# WIFI_and_BLE.net
KiCad netlist of a schematic drawn in Altium Designer
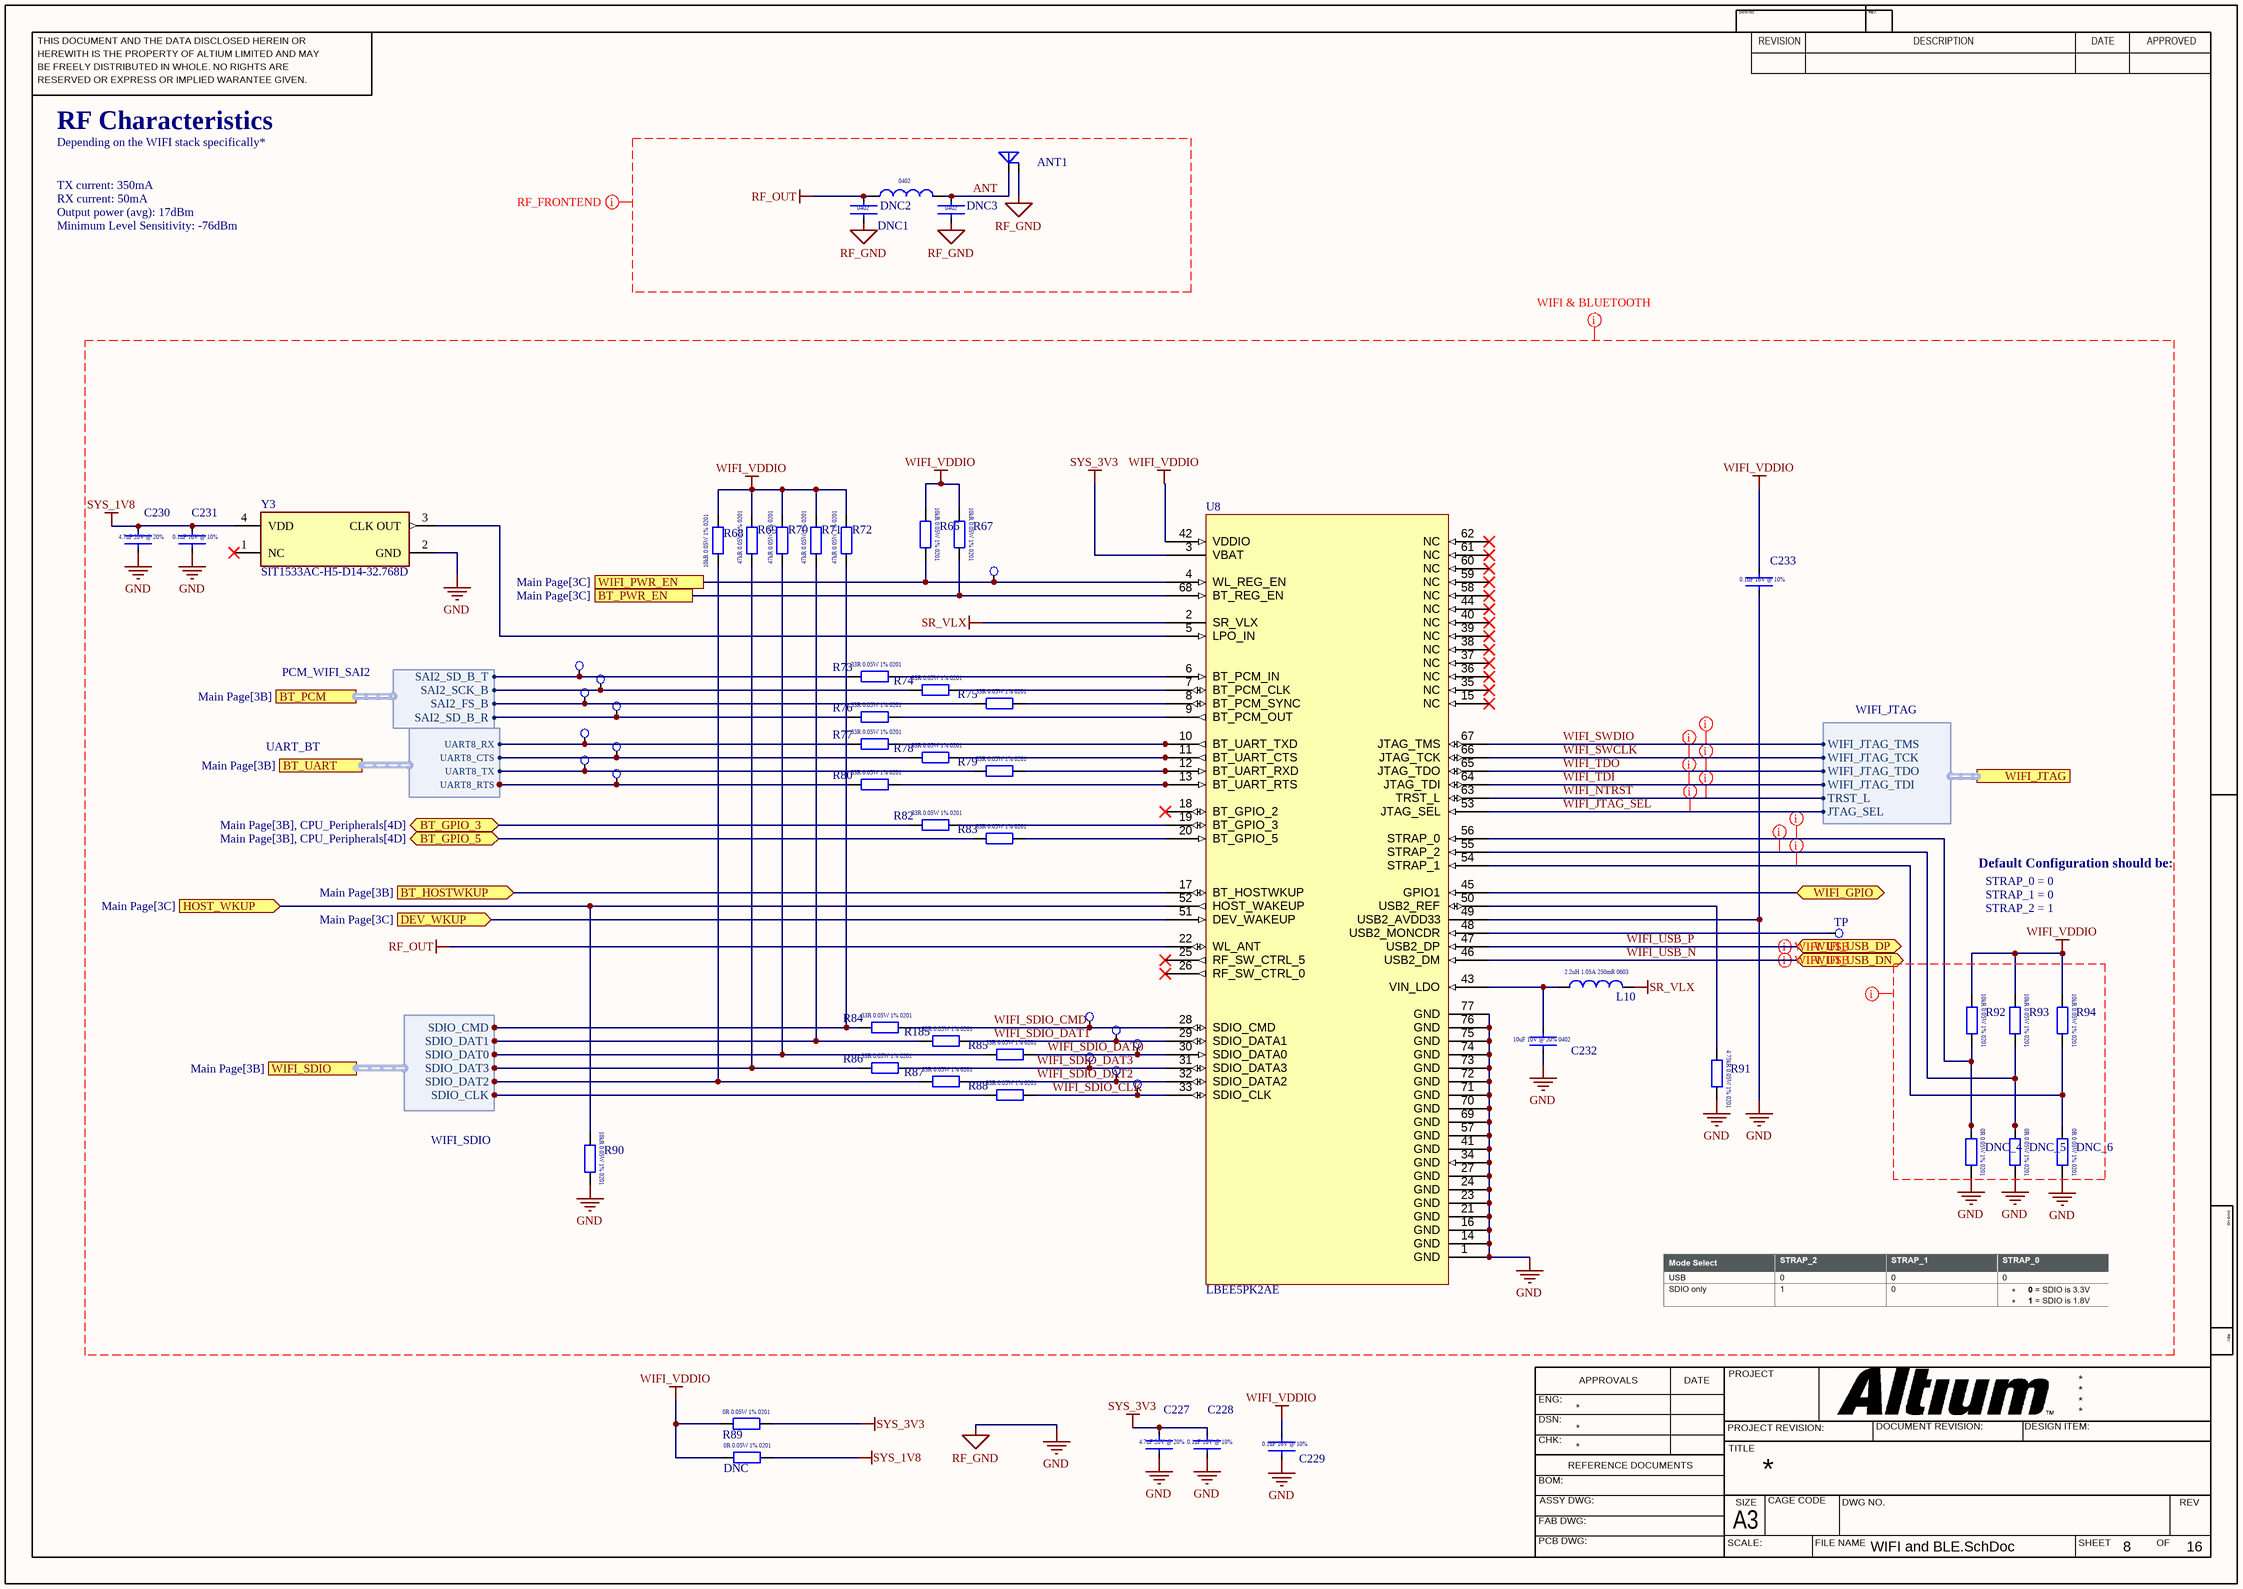
[diagram p0: WIFI and BLE.SchDoc]

(export (version "E")
  (design (tool "Eeschema 10.0.6"))
  (components
    (comp (ref "ANT1")
      (value "ANT5320LL24R2455A")
      (footprint "ANT5320LL24R2455A")
      (description "RF ANTENNA WLAN Chip Solder Surface Mount")
      (libsource (lib "Gesturelink Schematic Library") (part "ANT5320LL24R2455A"))
    )
    (comp (ref "C227")
      (value "4.7uF")
      (footprint "CAPC1005X06L")
      (description "4.7 µF ±20% 16V Ceramic Capacitor X5R 0402 (1005 Metric)")
      (libsource (lib "Gesturelink Schematic Library") (part "CL05A475MO5NUNC"))
    )
    (comp (ref "C228")
      (value "0.1uF")
      (footprint "CAPC0603X03L")
      (libsource (lib "Gesturelink Schematic Library") (part "GRM033R61E104KE14J"))
    )
    (comp (ref "C229")
      (value "0.1uF")
      (footprint "CAPC0603X03L")
      (libsource (lib "Gesturelink Schematic Library") (part "GRM033R61E104KE14J"))
    )
    (comp (ref "C230")
      (value "4.7uF")
      (footprint "CAPC1005X06L")
      (description "4.7 µF ±20% 16V Ceramic Capacitor X5R 0402 (1005 Metric)")
      (libsource (lib "Gesturelink Schematic Library") (part "CL05A475MO5NUNC"))
    )
    (comp (ref "C231")
      (value "0.1uF")
      (footprint "CAPC0603X03L")
      (libsource (lib "Gesturelink Schematic Library") (part "GRM033R61E104KE14J"))
    )
    (comp (ref "C232")
      (value "GRT155R61A106ME13J")
      (footprint "CAPC1005X06L")
      (description "10 µF ±20% 10V Ceramic Capacitor X5R 0402 (1005 Metric)")
      (libsource (lib "Capacitors") (part "GRT155R61A106ME13J"))
    )
    (comp (ref "C233")
      (value "0.1uF")
      (footprint "CAPC0603X03L")
      (libsource (lib "Gesturelink Schematic Library") (part "GRM033R61E104KE14J"))
    )
    (comp (ref "DNC")
      (value "ERJ-1GN0R00C")
      (footprint "RESC0603X03L")
      (description "0 Ohms Jumper Chip Resistor 0201 (0603 Metric) Thick Film")
      (libsource (lib "") (part "ERJ-1GN0R00C_1"))
    )
    (comp (ref "DNC1")
      (value "RF_GND_PI")
      (footprint "CAPC1005X06L")
      (description "Pi filter chip antenna, Do not connect!")
      (libsource (lib "Gesturelink Schematic Library") (part "RF_GND_PI"))
    )
    (comp (ref "DNC2")
      (value "DNC RF Inductor")
      (footprint "RESC1005X04L")
      (description "Inductor for PI filter, DNC")
      (libsource (lib "Inductors") (part "DNC RF Inductor"))
    )
    (comp (ref "DNC3")
      (value "RF_GND_PI")
      (footprint "CAPC1005X06L")
      (description "Pi filter chip antenna, Do not connect!")
      (libsource (lib "Gesturelink Schematic Library") (part "RF_GND_PI"))
    )
    (comp (ref "DNC_4")
      (value "ERJ-1GN0R00C")
      (footprint "RESC0603X03L")
      (description "0 Ohms Jumper Chip Resistor 0201 (0603 Metric) Thick Film")
      (libsource (lib "Resistors") (part "ERJ-1GN0R00C"))
    )
    (comp (ref "DNC_5")
      (value "ERJ-1GN0R00C")
      (footprint "RESC0603X03L")
      (description "0 Ohms Jumper Chip Resistor 0201 (0603 Metric) Thick Film")
      (libsource (lib "Resistors") (part "ERJ-1GN0R00C"))
    )
    (comp (ref "DNC_6")
      (value "ERJ-1GN0R00C")
      (footprint "RESC0603X03L")
      (description "0 Ohms Jumper Chip Resistor 0201 (0603 Metric) Thick Film")
      (libsource (lib "Resistors") (part "ERJ-1GN0R00C"))
    )
    (comp (ref "L10")
      (value "LQM18PN2R2MGHD")
      (footprint "INDC1608LPX08L")
      (description "2.2 µH Shielded Multilayer Inductor 1.05 A 250mOhm Max 0603 (1608 Metric)")
      (libsource (lib "Inductors") (part "LQM18PN2R2MGHD"))
    )
    (comp (ref "R66")
      (value "ERJ-1GNF1002C")
      (footprint "RESC0603X03L")
      (description "10 kOhms ±1% 0.05W, 1/20W Chip Resistor 0201 (0603 Metric) Thick Film")
      (libsource (lib "Resistors") (part "ERJ-1GNF1002C"))
    )
    (comp (ref "R67")
      (value "ERJ-1GNF1002C")
      (footprint "RESC0603X03L")
      (description "10 kOhms ±1% 0.05W, 1/20W Chip Resistor 0201 (0603 Metric) Thick Film")
      (libsource (lib "Resistors") (part "ERJ-1GNF1002C"))
    )
    (comp (ref "R68")
      (value "ERJ-1GNF1002C")
      (footprint "RESC0603X03L")
      (description "10 kOhms ±1% 0.05W, 1/20W Chip Resistor 0201 (0603 Metric) Thick Film")
      (libsource (lib "") (part "ERJ-1GNF1002C_1"))
    )
    (comp (ref "R69")
      (value "AC0201FR-0747KL")
      (footprint "RESC0603X03L")
      (libsource (lib "Resistors") (part "AC0201FR-0747KL"))
    )
    (comp (ref "R70")
      (value "AC0201FR-0747KL")
      (footprint "RESC0603X03L")
      (libsource (lib "Resistors") (part "AC0201FR-0747KL"))
    )
    (comp (ref "R71")
      (value "AC0201FR-0747KL")
      (footprint "RESC0603X03L")
      (libsource (lib "Resistors") (part "AC0201FR-0747KL"))
    )
    (comp (ref "R72")
      (value "AC0201FR-0747KL")
      (footprint "RESC0603X03L")
      (libsource (lib "Resistors") (part "AC0201FR-0747KL"))
    )
    (comp (ref "R73")
      (value "ERJ-1GNF33R0C")
      (footprint "RESC0603X03L")
      (description "33 Ohms ±1% 0.05W, 1/20W Chip Resistor 0201 (0603 Metric) Thick Film")
      (libsource (lib "Resistors") (part "ERJ-1GNF33R0C"))
    )
    (comp (ref "R74")
      (value "ERJ-1GNF33R0C")
      (footprint "RESC0603X03L")
      (description "33 Ohms ±1% 0.05W, 1/20W Chip Resistor 0201 (0603 Metric) Thick Film")
      (libsource (lib "Resistors") (part "ERJ-1GNF33R0C"))
    )
    (comp (ref "R75")
      (value "ERJ-1GNF33R0C")
      (footprint "RESC0603X03L")
      (description "33 Ohms ±1% 0.05W, 1/20W Chip Resistor 0201 (0603 Metric) Thick Film")
      (libsource (lib "Resistors") (part "ERJ-1GNF33R0C"))
    )
    (comp (ref "R76")
      (value "ERJ-1GNF33R0C")
      (footprint "RESC0603X03L")
      (description "33 Ohms ±1% 0.05W, 1/20W Chip Resistor 0201 (0603 Metric) Thick Film")
      (libsource (lib "Resistors") (part "ERJ-1GNF33R0C"))
    )
    (comp (ref "R77")
      (value "ERJ-1GNF33R0C")
      (footprint "RESC0603X03L")
      (description "33 Ohms ±1% 0.05W, 1/20W Chip Resistor 0201 (0603 Metric) Thick Film")
      (libsource (lib "Resistors") (part "ERJ-1GNF33R0C"))
    )
    (comp (ref "R78")
      (value "ERJ-1GNF33R0C")
      (footprint "RESC0603X03L")
      (description "33 Ohms ±1% 0.05W, 1/20W Chip Resistor 0201 (0603 Metric) Thick Film")
      (libsource (lib "Resistors") (part "ERJ-1GNF33R0C"))
    )
    (comp (ref "R79")
      (value "ERJ-1GNF33R0C")
      (footprint "RESC0603X03L")
      (description "33 Ohms ±1% 0.05W, 1/20W Chip Resistor 0201 (0603 Metric) Thick Film")
      (libsource (lib "Resistors") (part "ERJ-1GNF33R0C"))
    )
    (comp (ref "R80")
      (value "ERJ-1GNF33R0C")
      (footprint "RESC0603X03L")
      (description "33 Ohms ±1% 0.05W, 1/20W Chip Resistor 0201 (0603 Metric) Thick Film")
      (libsource (lib "Resistors") (part "ERJ-1GNF33R0C"))
    )
    (comp (ref "R82")
      (value "ERJ-1GNF33R0C")
      (footprint "RESC0603X03L")
      (description "33 Ohms ±1% 0.05W, 1/20W Chip Resistor 0201 (0603 Metric) Thick Film")
      (libsource (lib "Resistors") (part "ERJ-1GNF33R0C"))
    )
    (comp (ref "R83")
      (value "ERJ-1GNF33R0C")
      (footprint "RESC0603X03L")
      (description "33 Ohms ±1% 0.05W, 1/20W Chip Resistor 0201 (0603 Metric) Thick Film")
      (libsource (lib "Resistors") (part "ERJ-1GNF33R0C"))
    )
    (comp (ref "R84")
      (value "ERJ-1GNF33R0C")
      (footprint "RESC0603X03L")
      (description "33 Ohms ±1% 0.05W, 1/20W Chip Resistor 0201 (0603 Metric) Thick Film")
      (libsource (lib "Resistors") (part "ERJ-1GNF33R0C"))
    )
    (comp (ref "R85")
      (value "ERJ-1GNF33R0C")
      (footprint "RESC0603X03L")
      (description "33 Ohms ±1% 0.05W, 1/20W Chip Resistor 0201 (0603 Metric) Thick Film")
      (libsource (lib "Resistors") (part "ERJ-1GNF33R0C"))
    )
    (comp (ref "R86")
      (value "ERJ-1GNF33R0C")
      (footprint "RESC0603X03L")
      (description "33 Ohms ±1% 0.05W, 1/20W Chip Resistor 0201 (0603 Metric) Thick Film")
      (libsource (lib "Resistors") (part "ERJ-1GNF33R0C"))
    )
    (comp (ref "R87")
      (value "ERJ-1GNF33R0C")
      (footprint "RESC0603X03L")
      (description "33 Ohms ±1% 0.05W, 1/20W Chip Resistor 0201 (0603 Metric) Thick Film")
      (libsource (lib "Resistors") (part "ERJ-1GNF33R0C"))
    )
    (comp (ref "R88")
      (value "ERJ-1GNF33R0C")
      (footprint "RESC0603X03L")
      (description "33 Ohms ±1% 0.05W, 1/20W Chip Resistor 0201 (0603 Metric) Thick Film")
      (libsource (lib "Resistors") (part "ERJ-1GNF33R0C"))
    )
    (comp (ref "R89")
      (value "ERJ-1GN0R00C")
      (footprint "RESC0603X03L")
      (description "0 Ohms Jumper Chip Resistor 0201 (0603 Metric) Thick Film")
      (libsource (lib "") (part "ERJ-1GN0R00C_1"))
    )
    (comp (ref "R90")
      (value "ERJ-1GNF1002C")
      (footprint "RESC0603X03L")
      (description "10 kOhms ±1% 0.05W, 1/20W Chip Resistor 0201 (0603 Metric) Thick Film")
      (libsource (lib "Resistors") (part "ERJ-1GNF1002C"))
    )
    (comp (ref "R91")
      (value "AC0201FR-074K75L")
      (footprint "RESC0603X03L")
      (libsource (lib "Resistors") (part "AC0201FR-074K75L"))
    )
    (comp (ref "R92")
      (value "ERJ-1GNF1002C")
      (footprint "RESC0603X03L")
      (description "10 kOhms ±1% 0.05W, 1/20W Chip Resistor 0201 (0603 Metric) Thick Film")
      (libsource (lib "Resistors") (part "ERJ-1GNF1002C"))
    )
    (comp (ref "R93")
      (value "ERJ-1GNF1002C")
      (footprint "RESC0603X03L")
      (description "10 kOhms ±1% 0.05W, 1/20W Chip Resistor 0201 (0603 Metric) Thick Film")
      (libsource (lib "Resistors") (part "ERJ-1GNF1002C"))
    )
    (comp (ref "R94")
      (value "ERJ-1GNF1002C")
      (footprint "RESC0603X03L")
      (description "10 kOhms ±1% 0.05W, 1/20W Chip Resistor 0201 (0603 Metric) Thick Film")
      (libsource (lib "Resistors") (part "ERJ-1GNF1002C"))
    )
    (comp (ref "R185")
      (value "ERJ-1GNF33R0C")
      (footprint "RESC0603X03L")
      (description "33 Ohms ±1% 0.05W, 1/20W Chip Resistor 0201 (0603 Metric) Thick Film")
      (libsource (lib "Resistors") (part "ERJ-1GNF33R0C"))
    )
    (comp (ref "TP")
      (value "Test Point")
      (footprint "Test Point")
      (libsource (lib "Gesturelink Schematic Library") (part "Test Point"))
    )
    (comp (ref "TP1")
      (value "Test Point")
      (footprint "Test Point")
      (libsource (lib "Gesturelink Schematic Library") (part "Test Point"))
    )
    (comp (ref "TP2")
      (value "Test Point")
      (footprint "Test Point")
      (libsource (lib "Gesturelink Schematic Library") (part "Test Point"))
    )
    (comp (ref "TP3")
      (value "Test Point")
      (footprint "Test Point")
      (libsource (lib "Gesturelink Schematic Library") (part "Test Point"))
    )
    (comp (ref "TP4")
      (value "Test Point")
      (footprint "Test Point")
      (libsource (lib "Gesturelink Schematic Library") (part "Test Point"))
    )
    (comp (ref "TP5")
      (value "Test Point")
      (footprint "Test Point")
      (libsource (lib "Gesturelink Schematic Library") (part "Test Point"))
    )
    (comp (ref "TP6")
      (value "Test Point")
      (footprint "Test Point")
      (libsource (lib "Gesturelink Schematic Library") (part "Test Point"))
    )
    (comp (ref "TP21")
      (value "Test Point")
      (footprint "Test Point")
      (libsource (lib "Gesturelink Schematic Library") (part "Test Point"))
    )
    (comp (ref "TP22")
      (value "Test Point")
      (footprint "Test Point")
      (libsource (lib "Gesturelink Schematic Library") (part "Test Point"))
    )
    (comp (ref "TP23")
      (value "Test Point")
      (footprint "Test Point")
      (libsource (lib "Gesturelink Schematic Library") (part "Test Point"))
    )
    (comp (ref "TP24")
      (value "Test Point")
      (footprint "Test Point")
      (libsource (lib "Gesturelink Schematic Library") (part "Test Point"))
    )
    (comp (ref "TP25")
      (value "Test Point")
      (footprint "Test Point")
      (libsource (lib "Gesturelink Schematic Library") (part "Test Point"))
    )
    (comp (ref "TP26")
      (value "Test Point")
      (footprint "Test Point")
      (libsource (lib "Gesturelink Schematic Library") (part "Test Point"))
    )
    (comp (ref "TP27")
      (value "Test Point")
      (footprint "Test Point")
      (libsource (lib "Gesturelink Schematic Library") (part "Test Point"))
    )
    (comp (ref "TP28")
      (value "Test Point")
      (footprint "Test Point")
      (libsource (lib "Gesturelink Schematic Library") (part "Test Point"))
    )
    (comp (ref "TP40")
      (value "Test Point")
      (footprint "Test Point")
      (libsource (lib "Gesturelink Schematic Library") (part "Test Point"))
    )
    (comp (ref "U8")
      (value "LBEE5PK2AE")
      (footprint "LBEE5PK2AE")
      (libsource (lib "Gesturelink Schematic Library") (part "LBEE5PK2AE"))
    )
    (comp (ref "Y3")
      (value "SIT1533AC-H5-D14-32.768D")
      (footprint "FP-SiT1533-H-MFG")
      (description "MEMS OSC XO 32.7680KHZ LVCMOS")
      (libsource (lib "Altium Content Vault") (part "00febb3c8fa577a4e66d9d2e3688c3c"))
    )
  )
  (nets
    (net (code "5") (name "/ANT") (class "Default")
      (node (ref "ANT1") (pin "1") (pinfunction "FEED_1") (pintype "passive"))
      (node (ref "DNC2") (pin "2") (pinfunction "2_2") (pintype "passive"))
      (node (ref "DNC3") (pin "2") (pinfunction "2_2") (pintype "passive"))
    )
    (net (code "6") (name "/BT_GPIO_3") (class "Default")
      (node (ref "R82") (pin "1") (pinfunction "1_1") (pintype "passive"))
    )
    (net (code "7") (name "/BT_GPIO_5") (class "Default")
      (node (ref "R83") (pin "1") (pinfunction "1_1") (pintype "passive"))
    )
    (net (code "8") (name "/BT_HOSTWKUP") (class "Default")
      (node (ref "U8") (pin "17") (pinfunction "BT_HOSTWKUP_17") (pintype "bidirectional"))
    )
    (net (code "9") (name "/BT_PWR_EN") (class "Default")
      (node (ref "R67") (pin "2") (pinfunction "2_2") (pintype "passive"))
      (node (ref "U8") (pin "68") (pinfunction "BT_REG_EN_68") (pintype "input"))
    )
    (net (code "10") (name "/DEV_WKUP") (class "Default")
      (node (ref "U8") (pin "51") (pinfunction "DEV_WAKEUP_51") (pintype "input"))
    )
    (net (code "11") (name "/HOST_WKUP") (class "Default")
      (node (ref "R90") (pin "1") (pinfunction "1_1") (pintype "passive"))
      (node (ref "U8") (pin "52") (pinfunction "HOST_WAKEUP_52") (pintype "output"))
    )
    (net (code "12") (name "/SAI2_FS_B") (class "Default")
      (node (ref "R75") (pin "1") (pinfunction "1_1") (pintype "passive"))
      (node (ref "TP23") (pin "12") (pinfunction "12_12") (pintype "passive"))
    )
    (net (code "13") (name "/SAI2_SCK_B") (class "Default")
      (node (ref "R74") (pin "1") (pinfunction "1_1") (pintype "passive"))
      (node (ref "TP22") (pin "12") (pinfunction "12_12") (pintype "passive"))
    )
    (net (code "14") (name "/SAI2_SD_B_R") (class "Default")
      (node (ref "R76") (pin "1") (pinfunction "1_1") (pintype "passive"))
      (node (ref "TP24") (pin "12") (pinfunction "12_12") (pintype "passive"))
    )
    (net (code "15") (name "/SAI2_SD_B_T") (class "Default")
      (node (ref "R73") (pin "1") (pinfunction "1_1") (pintype "passive"))
      (node (ref "TP21") (pin "12") (pinfunction "12_12") (pintype "passive"))
    )
    (net (code "16") (name "/SDIO_CLK") (class "Default")
      (node (ref "R88") (pin "1") (pinfunction "1_1") (pintype "passive"))
    )
    (net (code "17") (name "/SDIO_CMD") (class "Default")
      (node (ref "R72") (pin "1") (pinfunction "1_1") (pintype "passive"))
      (node (ref "R84") (pin "1") (pinfunction "1_1") (pintype "passive"))
    )
    (net (code "18") (name "/SDIO_DAT0") (class "Default")
      (node (ref "R70") (pin "1") (pinfunction "1_1") (pintype "passive"))
      (node (ref "R85") (pin "1") (pinfunction "1_1") (pintype "passive"))
    )
    (net (code "19") (name "/SDIO_DAT1") (class "Default")
      (node (ref "R185") (pin "1") (pinfunction "1_1") (pintype "passive"))
      (node (ref "R71") (pin "1") (pinfunction "1_1") (pintype "passive"))
    )
    (net (code "20") (name "/SDIO_DAT2") (class "Default")
      (node (ref "R68") (pin "1") (pinfunction "1_1") (pintype "passive"))
      (node (ref "R87") (pin "1") (pinfunction "1_1") (pintype "passive"))
    )
    (net (code "21") (name "/SDIO_DAT3") (class "Default")
      (node (ref "R69") (pin "1") (pinfunction "1_1") (pintype "passive"))
      (node (ref "R86") (pin "1") (pinfunction "1_1") (pintype "passive"))
    )
    (net (code "22") (name "/UART8_CTS") (class "Default")
      (node (ref "R78") (pin "1") (pinfunction "1_1") (pintype "passive"))
      (node (ref "TP26") (pin "12") (pinfunction "12_12") (pintype "passive"))
    )
    (net (code "23") (name "/UART8_RTS") (class "Default")
      (node (ref "R80") (pin "1") (pinfunction "1_1") (pintype "passive"))
      (node (ref "TP28") (pin "12") (pinfunction "12_12") (pintype "passive"))
    )
    (net (code "24") (name "/UART8_RX") (class "Default")
      (node (ref "R77") (pin "1") (pinfunction "1_1") (pintype "passive"))
      (node (ref "TP25") (pin "12") (pinfunction "12_12") (pintype "passive"))
    )
    (net (code "25") (name "/UART8_TX") (class "Default")
      (node (ref "R79") (pin "1") (pinfunction "1_1") (pintype "passive"))
      (node (ref "TP27") (pin "12") (pinfunction "12_12") (pintype "passive"))
    )
    (net (code "26") (name "/WIFI_GPIO") (class "Default")
      (node (ref "U8") (pin "45") (pinfunction "GPIO1_45") (pintype "input"))
    )
    (net (code "27") (name "/WIFI_JTAG_SEL") (class "Default")
      (node (ref "U8") (pin "53") (pinfunction "JTAG_SEL_53") (pintype "input"))
    )
    (net (code "28") (name "/WIFI_NTRST") (class "Default")
      (node (ref "U8") (pin "63") (pinfunction "TRST_L_63") (pintype "bidirectional"))
    )
    (net (code "29") (name "/WIFI_PWR_EN") (class "Default")
      (node (ref "R66") (pin "2") (pinfunction "2_2") (pintype "passive"))
      (node (ref "TP40") (pin "12") (pinfunction "12_12") (pintype "passive"))
      (node (ref "U8") (pin "4") (pinfunction "WL_REG_EN_4") (pintype "input"))
    )
    (net (code "30") (name "/WIFI_SDIO_CLK") (class "Default")
      (node (ref "R88") (pin "2") (pinfunction "2_2") (pintype "passive"))
      (node (ref "TP6") (pin "12") (pinfunction "12_12") (pintype "passive"))
      (node (ref "U8") (pin "33") (pinfunction "SDIO_CLK_33") (pintype "bidirectional"))
    )
    (net (code "31") (name "/WIFI_SDIO_CMD") (class "Default")
      (node (ref "R84") (pin "2") (pinfunction "2_2") (pintype "passive"))
      (node (ref "TP1") (pin "12") (pinfunction "12_12") (pintype "passive"))
      (node (ref "U8") (pin "28") (pinfunction "SDIO_CMD_28") (pintype "bidirectional"))
    )
    (net (code "32") (name "/WIFI_SDIO_DAT0") (class "Default")
      (node (ref "R85") (pin "2") (pinfunction "2_2") (pintype "passive"))
      (node (ref "TP3") (pin "12") (pinfunction "12_12") (pintype "passive"))
      (node (ref "U8") (pin "30") (pinfunction "SDIO_DATA0_30") (pintype "input"))
    )
    (net (code "33") (name "/WIFI_SDIO_DAT1") (class "Default")
      (node (ref "R185") (pin "2") (pinfunction "2_2") (pintype "passive"))
      (node (ref "TP2") (pin "12") (pinfunction "12_12") (pintype "passive"))
      (node (ref "U8") (pin "29") (pinfunction "SDIO_DATA1_29") (pintype "bidirectional"))
    )
    (net (code "34") (name "/WIFI_SDIO_DAT2") (class "Default")
      (node (ref "R87") (pin "2") (pinfunction "2_2") (pintype "passive"))
      (node (ref "TP5") (pin "12") (pinfunction "12_12") (pintype "passive"))
      (node (ref "U8") (pin "32") (pinfunction "SDIO_DATA2_32") (pintype "bidirectional"))
    )
    (net (code "36") (name "/WIFI_SDIO_DAT3") (class "Default")
      (node (ref "R86") (pin "2") (pinfunction "2_2") (pintype "passive"))
      (node (ref "TP4") (pin "12") (pinfunction "12_12") (pintype "passive"))
      (node (ref "U8") (pin "31") (pinfunction "SDIO_DATA3_31") (pintype "bidirectional"))
    )
    (net (code "37") (name "/WIFI_SWCLK") (class "Default")
      (node (ref "U8") (pin "66") (pinfunction "JTAG_TCK_66") (pintype "bidirectional"))
    )
    (net (code "38") (name "/WIFI_SWDIO") (class "Default")
      (node (ref "U8") (pin "67") (pinfunction "JTAG_TMS_67") (pintype "bidirectional"))
    )
    (net (code "39") (name "/WIFI_TDI") (class "Default")
      (node (ref "U8") (pin "64") (pinfunction "JTAG_TDI_64") (pintype "bidirectional"))
    )
    (net (code "40") (name "/WIFI_TDO") (class "Default")
      (node (ref "U8") (pin "65") (pinfunction "JTAG_TDO_65") (pintype "bidirectional"))
    )
    (net (code "41") (name "/WIFI_USB_N") (class "Default")
      (node (ref "U8") (pin "46") (pinfunction "USB2_DM_46") (pintype "input"))
    )
    (net (code "46") (name "/WIFI_USB_P") (class "Default")
      (node (ref "U8") (pin "47") (pinfunction "USB2_DP_47") (pintype "input"))
    )
    (net (code "47") (name "GND") (class "Default")
      (node (ref "ANT1") (pin "3") (pinfunction "GND_3") (pintype "passive"))
      (node (ref "C227") (pin "1") (pinfunction "1_1") (pintype "passive"))
      (node (ref "C228") (pin "1") (pinfunction "1_1") (pintype "passive"))
      (node (ref "C229") (pin "1") (pinfunction "1_1") (pintype "passive"))
      (node (ref "C230") (pin "1") (pinfunction "1_1") (pintype "passive"))
      (node (ref "C231") (pin "1") (pinfunction "1_1") (pintype "passive"))
      (node (ref "C232") (pin "1") (pinfunction "1_1") (pintype "passive"))
      (node (ref "C233") (pin "1") (pinfunction "1_1") (pintype "passive"))
      (node (ref "DNC1") (pin "1") (pinfunction "1_1") (pintype "passive"))
      (node (ref "DNC3") (pin "1") (pinfunction "1_1") (pintype "passive"))
      (node (ref "DNC_4") (pin "2") (pinfunction "2_2") (pintype "passive"))
      (node (ref "DNC_5") (pin "2") (pinfunction "2_2") (pintype "passive"))
      (node (ref "DNC_6") (pin "2") (pinfunction "2_2") (pintype "passive"))
      (node (ref "R90") (pin "2") (pinfunction "2_2") (pintype "passive"))
      (node (ref "R91") (pin "2") (pinfunction "2_2") (pintype "passive"))
      (node (ref "U8") (pin "1") (pinfunction "GND_1") (pintype "power_in"))
      (node (ref "U8") (pin "14") (pinfunction "GND_14") (pintype "power_in"))
      (node (ref "U8") (pin "16") (pinfunction "GND_16") (pintype "power_in"))
      (node (ref "U8") (pin "21") (pinfunction "GND_21") (pintype "power_in"))
      (node (ref "U8") (pin "23") (pinfunction "GND_23") (pintype "power_in"))
      (node (ref "U8") (pin "24") (pinfunction "GND_24") (pintype "power_in"))
      (node (ref "U8") (pin "27") (pinfunction "GND_27") (pintype "power_in"))
      (node (ref "U8") (pin "34") (pinfunction "GND_34") (pintype "input"))
      (node (ref "U8") (pin "41") (pinfunction "GND_41") (pintype "power_in"))
      (node (ref "U8") (pin "49") (pinfunction "USB2_AVDD33_49") (pintype "power_in"))
      (node (ref "U8") (pin "57") (pinfunction "GND_57") (pintype "power_in"))
      (node (ref "U8") (pin "69") (pinfunction "GND_69") (pintype "power_in"))
      (node (ref "U8") (pin "70") (pinfunction "GND_70") (pintype "power_in"))
      (node (ref "U8") (pin "71") (pinfunction "GND_71") (pintype "power_in"))
      (node (ref "U8") (pin "72") (pinfunction "GND_72") (pintype "power_in"))
      (node (ref "U8") (pin "73") (pinfunction "GND_73") (pintype "power_in"))
      (node (ref "U8") (pin "74") (pinfunction "GND_74") (pintype "power_in"))
      (node (ref "U8") (pin "75") (pinfunction "GND_75") (pintype "power_in"))
      (node (ref "U8") (pin "76") (pinfunction "GND_76") (pintype "power_in"))
      (node (ref "U8") (pin "77") (pinfunction "GND_77") (pintype "power_in"))
      (node (ref "Y3") (pin "2") (pinfunction "GND_2") (pintype "power_in"))
    )
    (net (code "48") (name "Net-(U8-BT_GPIO_3)") (class "Default")
      (node (ref "R82") (pin "2") (pinfunction "2_2") (pintype "passive"))
      (node (ref "U8") (pin "19") (pinfunction "BT_GPIO_3_19") (pintype "bidirectional"))
    )
    (net (code "49") (name "Net-(U8-BT_GPIO_5)") (class "Default")
      (node (ref "R83") (pin "2") (pinfunction "2_2") (pintype "passive"))
      (node (ref "U8") (pin "20") (pinfunction "BT_GPIO_5_20") (pintype "input"))
    )
    (net (code "50") (name "Net-(U8-BT_PCM_CLK)") (class "Default")
      (node (ref "R74") (pin "2") (pinfunction "2_2") (pintype "passive"))
      (node (ref "U8") (pin "7") (pinfunction "BT_PCM_CLK_7") (pintype "bidirectional"))
    )
    (net (code "51") (name "Net-(U8-BT_PCM_IN)") (class "Default")
      (node (ref "R73") (pin "2") (pinfunction "2_2") (pintype "passive"))
      (node (ref "U8") (pin "6") (pinfunction "BT_PCM_IN_6") (pintype "input"))
    )
    (net (code "52") (name "Net-(U8-BT_PCM_OUT)") (class "Default")
      (node (ref "R76") (pin "2") (pinfunction "2_2") (pintype "passive"))
      (node (ref "U8") (pin "9") (pinfunction "BT_PCM_OUT_9") (pintype "output"))
    )
    (net (code "53") (name "Net-(U8-BT_PCM_SYNC)") (class "Default")
      (node (ref "R75") (pin "2") (pinfunction "2_2") (pintype "passive"))
      (node (ref "U8") (pin "8") (pinfunction "BT_PCM_SYNC_8") (pintype "bidirectional"))
    )
    (net (code "54") (name "Net-(U8-BT_UART_CTS)") (class "Default")
      (node (ref "R78") (pin "2") (pinfunction "2_2") (pintype "passive"))
      (node (ref "U8") (pin "11") (pinfunction "BT_UART_CTS_11") (pintype "output"))
    )
    (net (code "55") (name "Net-(U8-BT_UART_RTS)") (class "Default")
      (node (ref "R80") (pin "2") (pinfunction "2_2") (pintype "passive"))
      (node (ref "U8") (pin "13") (pinfunction "BT_UART_RTS_13") (pintype "input"))
    )
    (net (code "56") (name "Net-(U8-BT_UART_RXD)") (class "Default")
      (node (ref "R79") (pin "2") (pinfunction "2_2") (pintype "passive"))
      (node (ref "U8") (pin "12") (pinfunction "BT_UART_RXD_12") (pintype "input"))
    )
    (net (code "57") (name "Net-(U8-BT_UART_TXD)") (class "Default")
      (node (ref "R77") (pin "2") (pinfunction "2_2") (pintype "passive"))
      (node (ref "U8") (pin "10") (pinfunction "BT_UART_TXD_10") (pintype "output"))
    )
    (net (code "58") (name "Net-(U8-LPO_IN)") (class "Default")
      (node (ref "U8") (pin "5") (pinfunction "LPO_IN_5") (pintype "input"))
      (node (ref "Y3") (pin "3") (pinfunction "CLK_OUT_3") (pintype "output"))
    )
    (net (code "59") (name "Net-(U8-STRAP_0)") (class "Default")
      (node (ref "DNC_4") (pin "1") (pinfunction "1_1") (pintype "passive"))
      (node (ref "R92") (pin "2") (pinfunction "2_2") (pintype "passive"))
      (node (ref "U8") (pin "56") (pinfunction "STRAP_0_56") (pintype "input"))
    )
    (net (code "60") (name "Net-(U8-STRAP_1)") (class "Default")
      (node (ref "DNC_6") (pin "1") (pinfunction "1_1") (pintype "passive"))
      (node (ref "R94") (pin "2") (pinfunction "2_2") (pintype "passive"))
      (node (ref "U8") (pin "54") (pinfunction "STRAP_1_54") (pintype "input"))
    )
    (net (code "61") (name "Net-(U8-STRAP_2)") (class "Default")
      (node (ref "DNC_5") (pin "1") (pinfunction "1_1") (pintype "passive"))
      (node (ref "R93") (pin "2") (pinfunction "2_2") (pintype "passive"))
      (node (ref "U8") (pin "55") (pinfunction "STRAP_2_55") (pintype "input"))
    )
    (net (code "62") (name "Net-(U8-USB2_MONCDR)") (class "Default")
      (node (ref "TP") (pin "12") (pinfunction "12_12") (pintype "passive"))
      (node (ref "U8") (pin "48") (pinfunction "USB2_MONCDR_48") (pintype "input"))
    )
    (net (code "63") (name "Net-(U8-USB2_REF)") (class "Default")
      (node (ref "R91") (pin "1") (pinfunction "1_1") (pintype "passive"))
      (node (ref "U8") (pin "50") (pinfunction "USB2_REF_50") (pintype "bidirectional"))
    )
    (net (code "64") (name "Net-(U8-VIN_LDO)") (class "Default")
      (node (ref "C232") (pin "2") (pinfunction "2_2") (pintype "passive"))
      (node (ref "L10") (pin "1") (pinfunction "1_1") (pintype "passive"))
      (node (ref "U8") (pin "43") (pinfunction "VIN_LDO_43") (pintype "input"))
    )
    (net (code "65") (name "RF_OUT") (class "Default")
      (node (ref "DNC1") (pin "2") (pinfunction "2_2") (pintype "passive"))
      (node (ref "DNC2") (pin "1") (pinfunction "1_1") (pintype "passive"))
      (node (ref "U8") (pin "22") (pinfunction "WL_ANT_22") (pintype "bidirectional"))
    )
    (net (code "66") (name "SR_VLX") (class "Default")
      (node (ref "L10") (pin "2") (pinfunction "2_2") (pintype "passive"))
      (node (ref "U8") (pin "2") (pinfunction "SR_VLX_2") (pintype "power_in"))
    )
    (net (code "67") (name "SYS_1V8") (class "Default")
      (node (ref "C230") (pin "2") (pinfunction "2_2") (pintype "passive"))
      (node (ref "C231") (pin "2") (pinfunction "2_2") (pintype "passive"))
      (node (ref "DNC") (pin "2") (pinfunction "2_2") (pintype "passive"))
      (node (ref "Y3") (pin "4") (pinfunction "VDD_4") (pintype "power_in"))
    )
    (net (code "68") (name "SYS_3V3") (class "Default")
      (node (ref "C227") (pin "2") (pinfunction "2_2") (pintype "passive"))
      (node (ref "C228") (pin "2") (pinfunction "2_2") (pintype "passive"))
      (node (ref "R89") (pin "2") (pinfunction "2_2") (pintype "passive"))
      (node (ref "U8") (pin "3") (pinfunction "VBAT_3") (pintype "power_in"))
    )
    (net (code "69") (name "WIFI_VDDIO") (class "Default")
      (node (ref "C229") (pin "2") (pinfunction "2_2") (pintype "passive"))
      (node (ref "C233") (pin "2") (pinfunction "2_2") (pintype "passive"))
      (node (ref "DNC") (pin "1") (pinfunction "1_1") (pintype "passive"))
      (node (ref "R66") (pin "1") (pinfunction "1_1") (pintype "passive"))
      (node (ref "R67") (pin "1") (pinfunction "1_1") (pintype "passive"))
      (node (ref "R68") (pin "2") (pinfunction "2_2") (pintype "passive"))
      (node (ref "R69") (pin "2") (pinfunction "2_2") (pintype "passive"))
      (node (ref "R70") (pin "2") (pinfunction "2_2") (pintype "passive"))
      (node (ref "R71") (pin "2") (pinfunction "2_2") (pintype "passive"))
      (node (ref "R72") (pin "2") (pinfunction "2_2") (pintype "passive"))
      (node (ref "R89") (pin "1") (pinfunction "1_1") (pintype "passive"))
      (node (ref "R92") (pin "1") (pinfunction "1_1") (pintype "passive"))
      (node (ref "R93") (pin "1") (pinfunction "1_1") (pintype "passive"))
      (node (ref "R94") (pin "1") (pinfunction "1_1") (pintype "passive"))
      (node (ref "U8") (pin "42") (pinfunction "VDDIO_42") (pintype "input"))
    )
    (net (code "70") (name "unconnected-(U8-BT_GPIO_2-Pad18)") (class "Default")
      (node (ref "U8") (pin "18") (pinfunction "BT_GPIO_2_18") (pintype "bidirectional+no_connect"))
    )
    (net (code "71") (name "unconnected-(U8-NC-Pad15)") (class "Default")
      (node (ref "U8") (pin "15") (pinfunction "NC_15") (pintype "input+no_connect"))
    )
    (net (code "72") (name "unconnected-(U8-NC-Pad35)") (class "Default")
      (node (ref "U8") (pin "35") (pinfunction "NC_35") (pintype "input+no_connect"))
    )
    (net (code "73") (name "unconnected-(U8-NC-Pad36)") (class "Default")
      (node (ref "U8") (pin "36") (pinfunction "NC_36") (pintype "input+no_connect"))
    )
    (net (code "74") (name "unconnected-(U8-NC-Pad37)") (class "Default")
      (node (ref "U8") (pin "37") (pinfunction "NC_37") (pintype "input+no_connect"))
    )
    (net (code "75") (name "unconnected-(U8-NC-Pad38)") (class "Default")
      (node (ref "U8") (pin "38") (pinfunction "NC_38") (pintype "input+no_connect"))
    )
    (net (code "76") (name "unconnected-(U8-NC-Pad39)") (class "Default")
      (node (ref "U8") (pin "39") (pinfunction "NC_39") (pintype "input+no_connect"))
    )
    (net (code "77") (name "unconnected-(U8-NC-Pad40)") (class "Default")
      (node (ref "U8") (pin "40") (pinfunction "NC_40") (pintype "input+no_connect"))
    )
    (net (code "78") (name "unconnected-(U8-NC-Pad44)") (class "Default")
      (node (ref "U8") (pin "44") (pinfunction "NC_44") (pintype "input+no_connect"))
    )
    (net (code "79") (name "unconnected-(U8-NC-Pad58)") (class "Default")
      (node (ref "U8") (pin "58") (pinfunction "NC_58") (pintype "input+no_connect"))
    )
    (net (code "80") (name "unconnected-(U8-NC-Pad59)") (class "Default")
      (node (ref "U8") (pin "59") (pinfunction "NC_59") (pintype "input+no_connect"))
    )
    (net (code "81") (name "unconnected-(U8-NC-Pad60)") (class "Default")
      (node (ref "U8") (pin "60") (pinfunction "NC_60") (pintype "input+no_connect"))
    )
    (net (code "82") (name "unconnected-(U8-NC-Pad61)") (class "Default")
      (node (ref "U8") (pin "61") (pinfunction "NC_61") (pintype "input+no_connect"))
    )
    (net (code "83") (name "unconnected-(U8-NC-Pad62)") (class "Default")
      (node (ref "U8") (pin "62") (pinfunction "NC_62") (pintype "input+no_connect"))
    )
    (net (code "84") (name "unconnected-(U8-RF_SW_CTRL_0-Pad26)") (class "Default")
      (node (ref "U8") (pin "26") (pinfunction "RF_SW_CTRL_0_26") (pintype "output+no_connect"))
    )
    (net (code "85") (name "unconnected-(U8-RF_SW_CTRL_5-Pad25)") (class "Default")
      (node (ref "U8") (pin "25") (pinfunction "RF_SW_CTRL_5_25") (pintype "output+no_connect"))
    )
    (net (code "86") (name "unconnected-(Y3-NC-Pad1)") (class "Default")
      (node (ref "Y3") (pin "1") (pinfunction "NC_1") (pintype "passive+no_connect"))
    )
  )
)
